# Sensors.net
KiCad netlist of a schematic drawn in Altium Designer
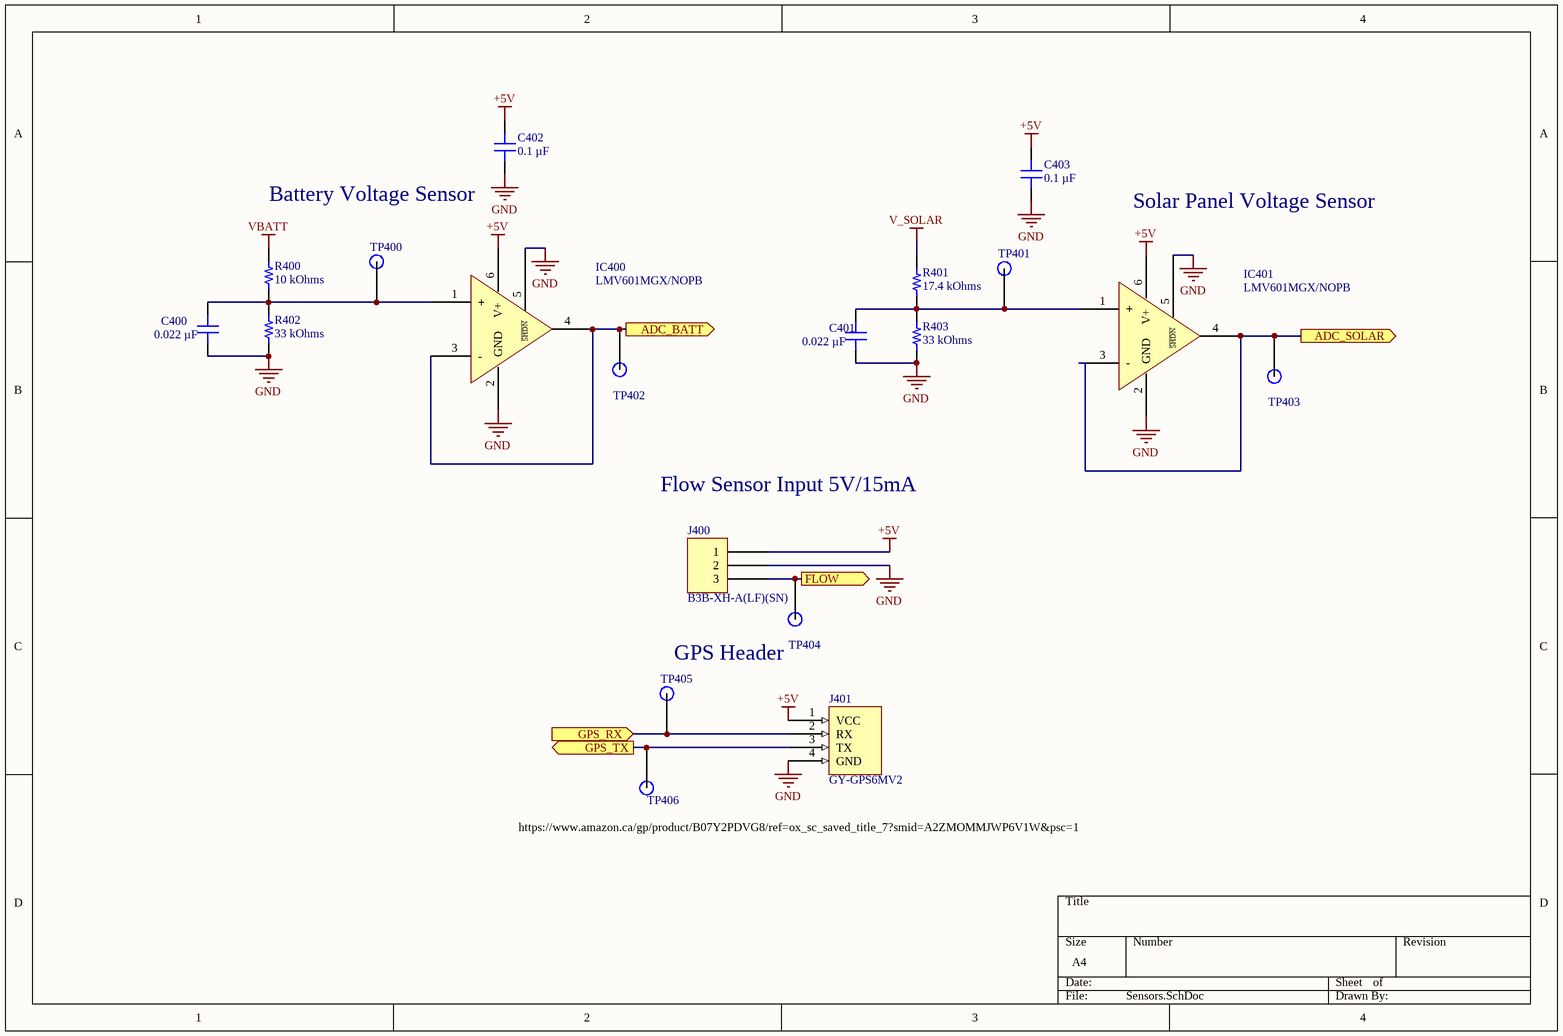
[diagram p0: Sensors.SchDoc]

(export (version "E")
  (design (tool "Eeschema 10.0.6"))
  (components
    (comp (ref "C400")
      (value "0.022 µF")
      (footprint "CAP 0603_1608")
      (description "CAP CER 0.022UF 16V X7R 0603")
      (fields (field (name "PART NUMBER") "CC0603KRX7R7BB223") (field (name "MANUFACTURER") "Yageo"))
      (libsource (lib "Celestial Altium Library - altium_library") (part "Capacitor"))
    )
    (comp (ref "C401")
      (value "0.022 µF")
      (footprint "CAP 0603_1608")
      (description "CAP CER 0.022UF 16V X7R 0603")
      (fields (field (name "PART NUMBER") "CC0603KRX7R7BB223") (field (name "MANUFACTURER") "Yageo"))
      (libsource (lib "Celestial Altium Library - altium_library") (part "Capacitor"))
    )
    (comp (ref "C402")
      (value "0.1 µF")
      (footprint "CAP 0603_1608")
      (description "CAP CER 0.1UF 25V X7R 0603")
      (fields (field (name "PART NUMBER") "C0603X104M3RAC7867") (field (name "MANUFACTURER") "KEMET"))
      (libsource (lib "Celestial Altium Library - altium_library") (part "Capacitor"))
    )
    (comp (ref "C403")
      (value "0.1 µF")
      (footprint "CAP 0603_1608")
      (description "CAP CER 0.1UF 25V X7R 0603")
      (fields (field (name "PART NUMBER") "C0603X104M3RAC7867") (field (name "MANUFACTURER") "KEMET"))
      (libsource (lib "Celestial Altium Library - altium_library") (part "Capacitor"))
    )
    (comp (ref "IC400")
      (value "LMV601MGX/NOPB")
      (footprint "TI SC70-6 DCK")
      (description "IC OPAMP GP 1 CIRCUIT SC70-6")
      (fields (field (name "MANUFACTURER") "Texas Instruments"))
      (libsource (lib "Celestial Altium Library - altium_library") (part "TI LMV601"))
    )
    (comp (ref "IC401")
      (value "LMV601MGX/NOPB")
      (footprint "TI SC70-6 DCK")
      (description "IC OPAMP GP 1 CIRCUIT SC70-6")
      (fields (field (name "MANUFACTURER") "Texas Instruments"))
      (libsource (lib "Celestial Altium Library - altium_library") (part "TI LMV601"))
    )
    (comp (ref "J400")
      (value "B3B-XH-A(LF)(SN)")
      (footprint "JST XH B3B-XH-A")
      (description "CONN HEADER VERT 3POS 2.5MM")
      (fields (field (name "MANUFACTURER") "JST Sales America Inc."))
      (libsource (lib "Celestial Altium Library - altium_library") (part "3 Pin"))
    )
    (comp (ref "J401")
      (value "GY-GPS6MV2")
      (footprint "GY-GPS6MV2 -Footprint-1")
      (description "NEO-6M GPS Module")
      (libsource (lib "Americas- Environmental Engineering Club- University of Victoria") (part "GY-GPS6MV2 -Symbol-1"))
    )
    (comp (ref "R400")
      (value "10 kOhms")
      (footprint "RES 0603_1608")
      (description "RES SMD 10K OHM 1% 1/10W 0603")
      (fields (field (name "PART NUMBER") "RT0603FRE0710KL") (field (name "MANUFACTURER") "Yageo"))
      (libsource (lib "Celestial Altium Library - altium_library") (part "Resistor"))
    )
    (comp (ref "R401")
      (value "17.4 kOhms")
      (footprint "RES 0603_1608")
      (description "RES 17.4K OHM 1% 1/10W 0603")
      (fields (field (name "PART NUMBER") "RC0603FR-0717K4L") (field (name "MANUFACTURER") "Yageo"))
      (libsource (lib "Celestial Altium Library - altium_library") (part "Resistor"))
    )
    (comp (ref "R402")
      (value "33 kOhms")
      (footprint "RES 0603_1608")
      (description "RES SMD 33K OHM 1% 1/10W 0603")
      (fields (field (name "PART NUMBER") "RT0603FRE0733KL") (field (name "MANUFACTURER") "Yageo"))
      (libsource (lib "Celestial Altium Library - altium_library") (part "Resistor"))
    )
    (comp (ref "R403")
      (value "33 kOhms")
      (footprint "RES 0603_1608")
      (description "RES SMD 33K OHM 1% 1/10W 0603")
      (fields (field (name "PART NUMBER") "RT0603FRE0733KL") (field (name "MANUFACTURER") "Yageo"))
      (libsource (lib "Celestial Altium Library - altium_library") (part "Resistor"))
    )
    (comp (ref "TP400")
      (value "1.5mm Test Point")
      (footprint "1mm Test Point-Footprint-1")
      (description "1.5mm Test Point 0.75mm hole size")
      (libsource (lib "Americas- Environmental Engineering Club- University of Victoria") (part "1mm Test Point-Symbol-1"))
    )
    (comp (ref "TP401")
      (value "1.5mm Test Point")
      (footprint "1mm Test Point-Footprint-1")
      (description "1.5mm Test Point 0.75mm hole size")
      (libsource (lib "Americas- Environmental Engineering Club- University of Victoria") (part "1mm Test Point-Symbol-1"))
    )
    (comp (ref "TP402")
      (value "1.5mm Test Point")
      (footprint "1mm Test Point-Footprint-1")
      (description "1.5mm Test Point 0.75mm hole size")
      (libsource (lib "Americas- Environmental Engineering Club- University of Victoria") (part "1mm Test Point-Symbol-1"))
    )
    (comp (ref "TP403")
      (value "1.5mm Test Point")
      (footprint "1mm Test Point-Footprint-1")
      (description "1.5mm Test Point 0.75mm hole size")
      (libsource (lib "Americas- Environmental Engineering Club- University of Victoria") (part "1mm Test Point-Symbol-1"))
    )
    (comp (ref "TP404")
      (value "1.5mm Test Point")
      (footprint "1mm Test Point-Footprint-1")
      (description "1.5mm Test Point 0.75mm hole size")
      (libsource (lib "Americas- Environmental Engineering Club- University of Victoria") (part "1mm Test Point-Symbol-1"))
    )
    (comp (ref "TP405")
      (value "1.5mm Test Point")
      (footprint "1mm Test Point-Footprint-1")
      (description "1.5mm Test Point 0.75mm hole size")
      (libsource (lib "Americas- Environmental Engineering Club- University of Victoria") (part "1mm Test Point-Symbol-1"))
    )
    (comp (ref "TP406")
      (value "1.5mm Test Point")
      (footprint "1mm Test Point-Footprint-1")
      (description "1.5mm Test Point 0.75mm hole size")
      (libsource (lib "Americas- Environmental Engineering Club- University of Victoria") (part "1mm Test Point-Symbol-1"))
    )
  )
  (nets
    (net (code "1") (name "+5V") (class "Default")
      (node (ref "C402") (pin "2") (pinfunction "2_2") (pintype "passive"))
      (node (ref "C403") (pin "2") (pinfunction "2_2") (pintype "passive"))
      (node (ref "IC400") (pin "6") (pinfunction "V+_6") (pintype "power_in"))
      (node (ref "IC401") (pin "6") (pinfunction "V+_6") (pintype "power_in"))
      (node (ref "J400") (pin "1") (pinfunction "1_1") (pintype "passive"))
      (node (ref "J401") (pin "1") (pinfunction "VCC_1") (pintype "input"))
    )
    (net (code "2") (name "/ADC_BATT") (class "Default")
      (node (ref "IC400") (pin "3") (pinfunction "-_3") (pintype "passive"))
      (node (ref "IC400") (pin "4") (pinfunction "OUT_4") (pintype "passive"))
      (node (ref "TP402") (pin "1") (pinfunction "1_1") (pintype "passive"))
    )
    (net (code "3") (name "/ADC_SOLAR") (class "Default")
      (node (ref "IC401") (pin "3") (pinfunction "-_3") (pintype "passive"))
      (node (ref "IC401") (pin "4") (pinfunction "OUT_4") (pintype "passive"))
      (node (ref "TP403") (pin "1") (pinfunction "1_1") (pintype "passive"))
    )
    (net (code "4") (name "/FLOW") (class "Default")
      (node (ref "J400") (pin "3") (pinfunction "3_3") (pintype "passive"))
      (node (ref "TP404") (pin "1") (pinfunction "1_1") (pintype "passive"))
    )
    (net (code "5") (name "/GPS_RX") (class "Default")
      (node (ref "J401") (pin "2") (pinfunction "RX_2") (pintype "input"))
      (node (ref "TP405") (pin "1") (pinfunction "1_1") (pintype "passive"))
    )
    (net (code "6") (name "/GPS_TX") (class "Default")
      (node (ref "J401") (pin "3") (pinfunction "TX_3") (pintype "input"))
      (node (ref "TP406") (pin "1") (pinfunction "1_1") (pintype "passive"))
    )
    (net (code "7") (name "GND") (class "Default")
      (node (ref "C400") (pin "1") (pinfunction "1_1") (pintype "passive"))
      (node (ref "C401") (pin "1") (pinfunction "1_1") (pintype "passive"))
      (node (ref "C402") (pin "1") (pinfunction "1_1") (pintype "passive"))
      (node (ref "C403") (pin "1") (pinfunction "1_1") (pintype "passive"))
      (node (ref "IC400") (pin "2") (pinfunction "GND_2") (pintype "power_in"))
      (node (ref "IC400") (pin "5") (pinfunction "~{SHDN}_5") (pintype "passive"))
      (node (ref "IC401") (pin "2") (pinfunction "GND_2") (pintype "power_in"))
      (node (ref "IC401") (pin "5") (pinfunction "~{SHDN}_5") (pintype "passive"))
      (node (ref "J400") (pin "2") (pinfunction "2_2") (pintype "passive"))
      (node (ref "J401") (pin "4") (pinfunction "GND_4") (pintype "input"))
      (node (ref "R402") (pin "1") (pinfunction "1_1") (pintype "passive"))
      (node (ref "R403") (pin "1") (pinfunction "1_1") (pintype "passive"))
    )
    (net (code "8") (name "Net-(IC400-+)") (class "Default")
      (node (ref "C400") (pin "2") (pinfunction "2_2") (pintype "passive"))
      (node (ref "IC400") (pin "1") (pinfunction "+_1") (pintype "passive"))
      (node (ref "R400") (pin "1") (pinfunction "1_1") (pintype "passive"))
      (node (ref "R402") (pin "2") (pinfunction "2_2") (pintype "passive"))
      (node (ref "TP400") (pin "1") (pinfunction "1_1") (pintype "passive"))
    )
    (net (code "9") (name "Net-(IC401-+)") (class "Default")
      (node (ref "C401") (pin "2") (pinfunction "2_2") (pintype "passive"))
      (node (ref "IC401") (pin "1") (pinfunction "+_1") (pintype "passive"))
      (node (ref "R401") (pin "1") (pinfunction "1_1") (pintype "passive"))
      (node (ref "R403") (pin "2") (pinfunction "2_2") (pintype "passive"))
      (node (ref "TP401") (pin "1") (pinfunction "1_1") (pintype "passive"))
    )
    (net (code "10") (name "VBATT") (class "Default")
      (node (ref "R400") (pin "2") (pinfunction "2_2") (pintype "passive"))
    )
    (net (code "11") (name "V_SOLAR") (class "Default")
      (node (ref "R401") (pin "2") (pinfunction "2_2") (pintype "passive"))
    )
  )
)
